# Strobe.net
KiCad netlist of a schematic drawn in EAGLE
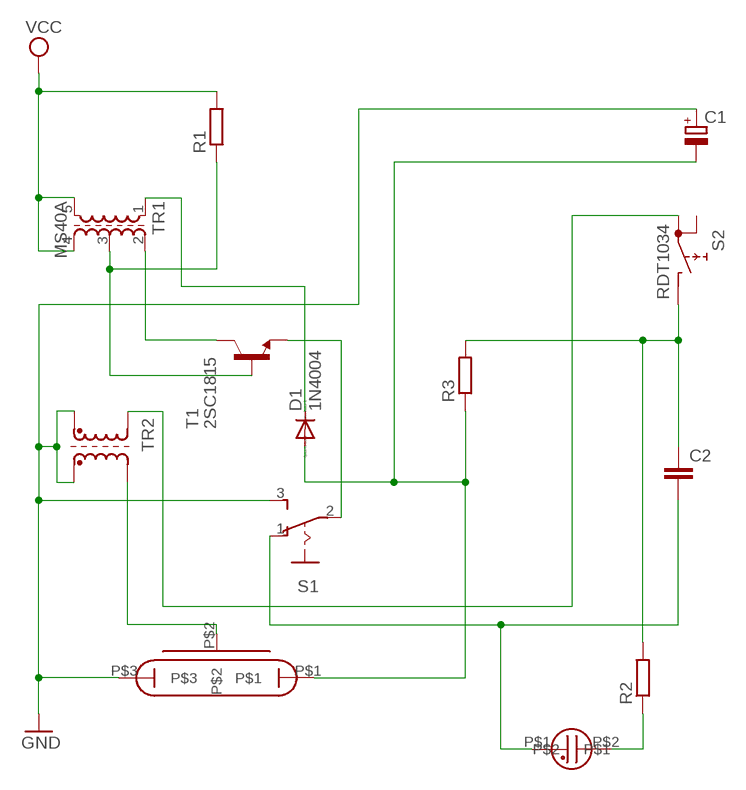
[diagram p0: schematic, sheet 1]

(export (version "E")
  (design (tool "Eeschema 10.0.6"))
  (components
    (comp (ref "C1")
      (value "CPOL-EU140CLH-0810")
      (footprint "eagle-import:140CLH-0810")
      (libsource (lib "eagle-import") (part "CPOL-EU140CLH-0810"))
    )
    (comp (ref "C2")
      (value "C-EU150-054X183")
      (footprint "eagle-import:C150-054X183")
      (libsource (lib "eagle-import") (part "C-EU150-054X183"))
    )
    (comp (ref "D1")
      (value "1N4004")
      (footprint "eagle-import:DO41-10")
      (libsource (lib "eagle-import") (part "1N4004"))
    )
    (comp (ref "R1")
      (value "R-EU_0204/2V")
      (footprint "eagle-import:0204V")
      (libsource (lib "eagle-import") (part "R-EU_0204/2V"))
    )
    (comp (ref "R2")
      (value "R-EU_0204/2V")
      (footprint "eagle-import:0204V")
      (libsource (lib "eagle-import") (part "R-EU_0204/2V"))
    )
    (comp (ref "R3")
      (value "R-EU_0204/2V")
      (footprint "eagle-import:0204V")
      (libsource (lib "eagle-import") (part "R-EU_0204/2V"))
    )
    (comp (ref "S1")
      (value "255SB")
      (footprint "eagle-import:255SB")
      (libsource (lib "eagle-import") (part "255SB"))
    )
    (comp (ref "S2")
      (value "RDT1034")
      (footprint "eagle-import:RDT1034")
      (libsource (lib "eagle-import") (part "RDT1034"))
    )
    (comp (ref "T1")
      (value "2SC1815")
      (footprint "eagle-import:TO92-ECB")
      (libsource (lib "eagle-import") (part "2SC1815"))
    )
    (comp (ref "TR1")
      (value "MS40A")
      (footprint "eagle-import:MS40")
      (libsource (lib "eagle-import") (part "MS40A"))
    )
    (comp (ref "TR2")
      (value "SM-T4")
      (footprint "eagle-import:SM-T4")
      (libsource (lib "eagle-import") (part "SM-T4"))
    )
    (comp (ref "U$1")
      (value "XENON")
      (footprint "eagle-import:XENON")
      (libsource (lib "eagle-import") (part "XENON"))
    )
    (comp (ref "U$2")
      (value "NEON")
      (footprint "eagle-import:NEON")
      (libsource (lib "eagle-import") (part "NEON"))
    )
  )
  (nets
    (net (code "1") (name "GND") (class "Default")
      (node (ref "C1") (pin "+") (pinfunction "+_+") (pintype "passive"))
      (node (ref "S1") (pin "3") (pinfunction "S_3") (pintype "passive"))
      (node (ref "TR2") (pin "2") (pinfunction "E1_2") (pintype "passive"))
      (node (ref "TR2") (pin "4") (pinfunction "E2_4") (pintype "passive"))
      (node (ref "U$1") (pin "P$3") (pinfunction "P$3_P$3") (pintype "bidirectional"))
    )
    (net (code "2") (name "Net-(C1-Pad-)") (class "Default")
      (node (ref "C1") (pin "-") (pinfunction "-_-") (pintype "passive"))
      (node (ref "D1") (pin "A") (pinfunction "A_A") (pintype "passive"))
      (node (ref "R3") (pin "1") (pinfunction "1_1") (pintype "passive"))
      (node (ref "U$1") (pin "P$1") (pinfunction "P$1_P$1") (pintype "bidirectional"))
    )
    (net (code "3") (name "Net-(C2-Pad1)") (class "Default")
      (node (ref "C2") (pin "1") (pinfunction "1_1") (pintype "passive"))
      (node (ref "R2") (pin "2") (pinfunction "2_2") (pintype "passive"))
      (node (ref "R3") (pin "2") (pinfunction "2_2") (pintype "passive"))
      (node (ref "S2") (pin "B") (pinfunction "B_B") (pintype "passive"))
    )
    (net (code "4") (name "Net-(D1-PadC)") (class "Default")
      (node (ref "D1") (pin "C") (pinfunction "C_C") (pintype "passive"))
      (node (ref "TR1") (pin "1") (pinfunction "1_1") (pintype "passive"))
    )
    (net (code "5") (name "Net-(R1-Pad1)") (class "Default")
      (node (ref "R1") (pin "1") (pinfunction "1_1") (pintype "passive"))
      (node (ref "T1") (pin "B") (pinfunction "B_B") (pintype "passive"))
      (node (ref "TR1") (pin "3") (pinfunction "3_3") (pintype "passive"))
    )
    (net (code "6") (name "Net-(R2-Pad1)") (class "Default")
      (node (ref "R2") (pin "1") (pinfunction "1_1") (pintype "passive"))
      (node (ref "U$2") (pin "P$2") (pinfunction "P$2_P$2") (pintype "bidirectional"))
    )
    (net (code "7") (name "Net-(S1-O)") (class "Default")
      (node (ref "C2") (pin "2") (pinfunction "2_2") (pintype "passive"))
      (node (ref "S1") (pin "1") (pinfunction "O_1") (pintype "passive"))
      (node (ref "U$2") (pin "P$1") (pinfunction "P$1_P$1") (pintype "bidirectional"))
    )
    (net (code "8") (name "Net-(S1-P)") (class "Default")
      (node (ref "S1") (pin "2") (pinfunction "P_2") (pintype "passive"))
      (node (ref "T1") (pin "E") (pinfunction "E_E") (pintype "passive"))
    )
    (net (code "9") (name "Net-(T1-PadC)") (class "Default")
      (node (ref "T1") (pin "C") (pinfunction "C_C") (pintype "passive"))
      (node (ref "TR1") (pin "2") (pinfunction "2_2") (pintype "passive"))
    )
    (net (code "10") (name "Net-(TR2-A1)") (class "Default")
      (node (ref "S2") (pin "A1") (pinfunction "A1_A1") (pintype "passive"))
      (node (ref "TR2") (pin "1") (pinfunction "A1_1") (pintype "passive"))
    )
    (net (code "11") (name "Net-(TR2-A2)") (class "Default")
      (node (ref "TR2") (pin "5") (pinfunction "A2_5") (pintype "passive"))
      (node (ref "U$1") (pin "P$2") (pinfunction "P$2_P$2") (pintype "bidirectional"))
    )
    (net (code "12") (name "VCC") (class "Default")
      (node (ref "R1") (pin "2") (pinfunction "2_2") (pintype "passive"))
      (node (ref "TR1") (pin "4") (pinfunction "4_4") (pintype "passive"))
      (node (ref "TR1") (pin "5") (pinfunction "5_5") (pintype "passive"))
    )
    (net (code "13") (name "unconnected-(S2-PadA)") (class "Default")
      (node (ref "S2") (pin "A") (pinfunction "A_A") (pintype "passive"))
    )
  )
)
